# Pro_Micro_ISP.net
KiCad netlist of a schematic drawn in EAGLE
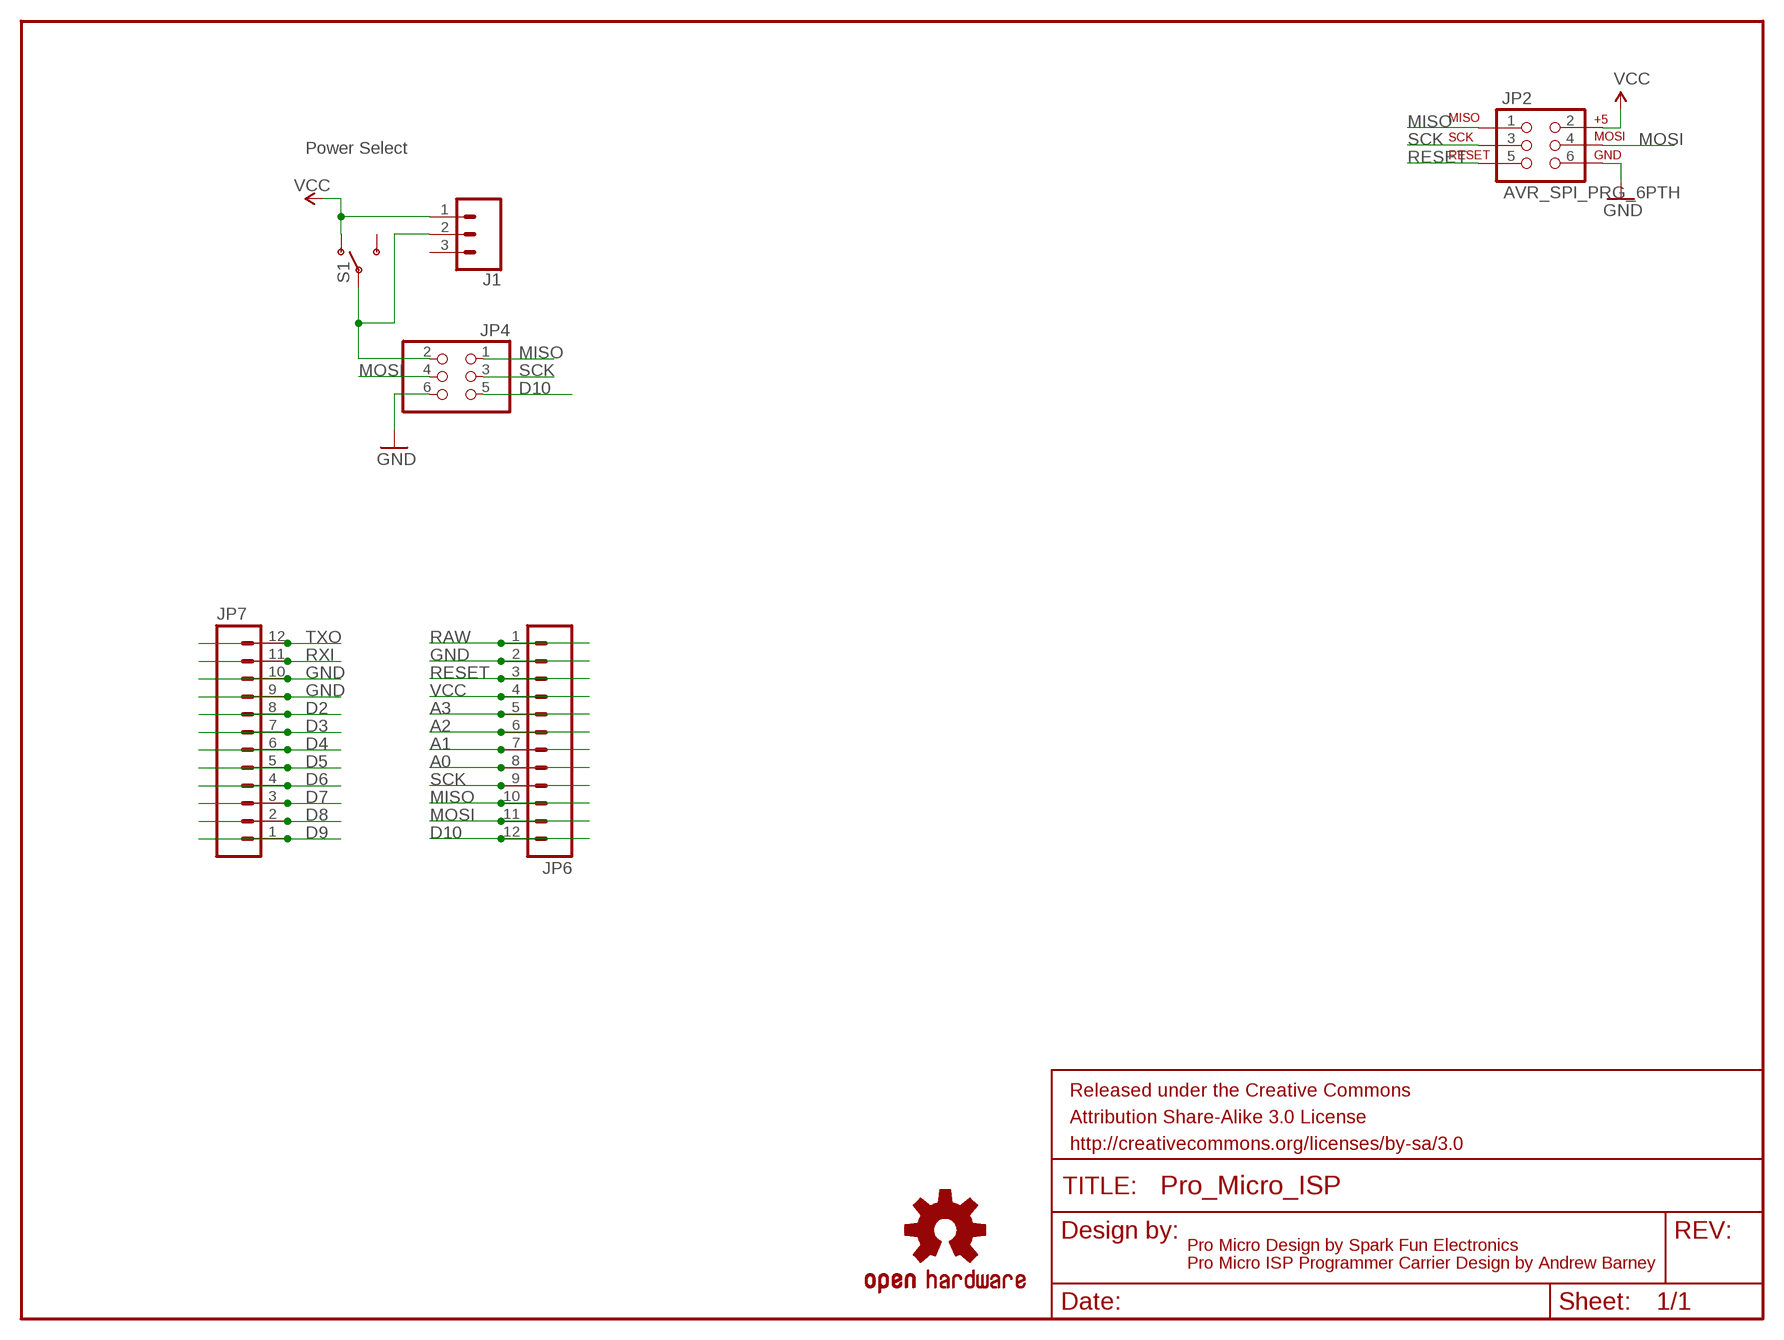
[diagram p0: schematic, sheet 1]

(export (version "E")
  (design (tool "Eeschema 10.0.6"))
  (components
    (comp (ref "FRAME1")
      (value "FRAME-LETTER")
      (footprint "eagle-import:CREATIVE_COMMONS")
      (libsource (lib "eagle-import") (part "FRAME-LETTER"))
    )
    (comp (ref "J1")
      (value "CONN_03")
      (footprint "eagle-import:1X03")
      (libsource (lib "eagle-import") (part "CONN_03"))
    )
    (comp (ref "JP2")
      (value "AVR_SPI_PRG_6PTH")
      (footprint "eagle-import:2X3")
      (libsource (lib "eagle-import") (part "AVR_SPI_PRG_6PTH"))
    )
    (comp (ref "JP4")
      (value "PINHD-2X3")
      (footprint "eagle-import:2X03")
      (libsource (lib "eagle-import") (part "PINHD-2X3"))
    )
    (comp (ref "JP6")
      (value "M12PTH")
      (footprint "eagle-import:1X12")
      (libsource (lib "eagle-import") (part "M12PTH"))
    )
    (comp (ref "JP7")
      (value "M12PTH")
      (footprint "eagle-import:1X12")
      (libsource (lib "eagle-import") (part "M12PTH"))
    )
    (comp (ref "S1")
      (value "Power Select")
      (footprint "eagle-import:AYZ0202")
      (libsource (lib "eagle-import") (part "SWITCH-SPSTSMD"))
    )
    (comp (ref "U$3")
      (value "OSHW-LOGOS")
      (footprint "eagle-import:OSHW-LOGO-S")
      (libsource (lib "eagle-import") (part "OSHW-LOGOS"))
    )
  )
  (nets
    (net (code "1") (name "/A0") (class "Default")
      (node (ref "JP6") (pin "8") (pinfunction "8_8") (pintype "passive"))
    )
    (net (code "2") (name "/A1") (class "Default")
      (node (ref "JP6") (pin "7") (pinfunction "7_7") (pintype "passive"))
    )
    (net (code "3") (name "/A2") (class "Default")
      (node (ref "JP6") (pin "6") (pinfunction "6_6") (pintype "passive"))
    )
    (net (code "4") (name "/A3") (class "Default")
      (node (ref "JP6") (pin "5") (pinfunction "5_5") (pintype "passive"))
    )
    (net (code "5") (name "/D2") (class "Default")
      (node (ref "JP7") (pin "8") (pinfunction "8_8") (pintype "passive"))
    )
    (net (code "6") (name "/D3") (class "Default")
      (node (ref "JP7") (pin "7") (pinfunction "7_7") (pintype "passive"))
    )
    (net (code "7") (name "/D4") (class "Default")
      (node (ref "JP7") (pin "6") (pinfunction "6_6") (pintype "passive"))
    )
    (net (code "8") (name "/D5") (class "Default")
      (node (ref "JP7") (pin "5") (pinfunction "5_5") (pintype "passive"))
    )
    (net (code "9") (name "/D6") (class "Default")
      (node (ref "JP7") (pin "4") (pinfunction "4_4") (pintype "passive"))
    )
    (net (code "10") (name "/D7") (class "Default")
      (node (ref "JP7") (pin "3") (pinfunction "3_3") (pintype "passive"))
    )
    (net (code "11") (name "/D8") (class "Default")
      (node (ref "JP7") (pin "2") (pinfunction "2_2") (pintype "passive"))
    )
    (net (code "12") (name "/D9") (class "Default")
      (node (ref "JP7") (pin "1") (pinfunction "1_1") (pintype "passive"))
    )
    (net (code "13") (name "/D10") (class "Default")
      (node (ref "JP4") (pin "5") (pinfunction "5_5") (pintype "passive"))
      (node (ref "JP6") (pin "12") (pinfunction "12_12") (pintype "passive"))
    )
    (net (code "14") (name "/MISO") (class "Default")
      (node (ref "JP2") (pin "1") (pinfunction "1_1") (pintype "passive"))
      (node (ref "JP4") (pin "1") (pinfunction "1_1") (pintype "passive"))
      (node (ref "JP6") (pin "10") (pinfunction "10_10") (pintype "passive"))
    )
    (net (code "15") (name "/MOSI") (class "Default")
      (node (ref "JP2") (pin "4") (pinfunction "4_4") (pintype "passive"))
      (node (ref "JP4") (pin "4") (pinfunction "4_4") (pintype "passive"))
      (node (ref "JP6") (pin "11") (pinfunction "11_11") (pintype "passive"))
    )
    (net (code "16") (name "/RAW") (class "Default")
      (node (ref "JP6") (pin "1") (pinfunction "1_1") (pintype "passive"))
    )
    (net (code "17") (name "/RESET") (class "Default")
      (node (ref "JP2") (pin "5") (pinfunction "5_5") (pintype "passive"))
      (node (ref "JP6") (pin "3") (pinfunction "3_3") (pintype "passive"))
    )
    (net (code "18") (name "/RXI") (class "Default")
      (node (ref "JP7") (pin "11") (pinfunction "11_11") (pintype "passive"))
    )
    (net (code "19") (name "/SCK") (class "Default")
      (node (ref "JP2") (pin "3") (pinfunction "3_3") (pintype "passive"))
      (node (ref "JP4") (pin "3") (pinfunction "3_3") (pintype "passive"))
      (node (ref "JP6") (pin "9") (pinfunction "9_9") (pintype "passive"))
    )
    (net (code "20") (name "/TXO") (class "Default")
      (node (ref "JP7") (pin "12") (pinfunction "12_12") (pintype "passive"))
    )
    (net (code "21") (name "GND") (class "Default")
      (node (ref "JP2") (pin "6") (pinfunction "6_6") (pintype "passive"))
      (node (ref "JP4") (pin "6") (pinfunction "6_6") (pintype "passive"))
      (node (ref "JP6") (pin "2") (pinfunction "2_2") (pintype "passive"))
      (node (ref "JP7") (pin "10") (pinfunction "10_10") (pintype "passive"))
      (node (ref "JP7") (pin "9") (pinfunction "9_9") (pintype "passive"))
    )
    (net (code "22") (name "Net-(S1-P)") (class "Default")
      (node (ref "J1") (pin "2") (pinfunction "2_2") (pintype "passive"))
      (node (ref "JP4") (pin "2") (pinfunction "2_2") (pintype "passive"))
      (node (ref "S1") (pin "2") (pinfunction "P_2") (pintype "passive"))
    )
    (net (code "23") (name "VCC") (class "Default")
      (node (ref "J1") (pin "1") (pinfunction "1_1") (pintype "passive"))
      (node (ref "JP2") (pin "2") (pinfunction "2_2") (pintype "passive"))
      (node (ref "JP6") (pin "4") (pinfunction "4_4") (pintype "passive"))
      (node (ref "S1") (pin "1") (pinfunction "O_1") (pintype "passive"))
    )
    (net (code "24") (name "unconnected-(J1-Pad3)") (class "Default")
      (node (ref "J1") (pin "3") (pinfunction "3_3") (pintype "passive"))
    )
    (net (code "25") (name "unconnected-(S1-S-Pad3)") (class "Default")
      (node (ref "S1") (pin "3") (pinfunction "S_3") (pintype "passive"))
    )
  )
)
